# PowerMinder1sch.net
KiCad netlist of a schematic drawn in EAGLE
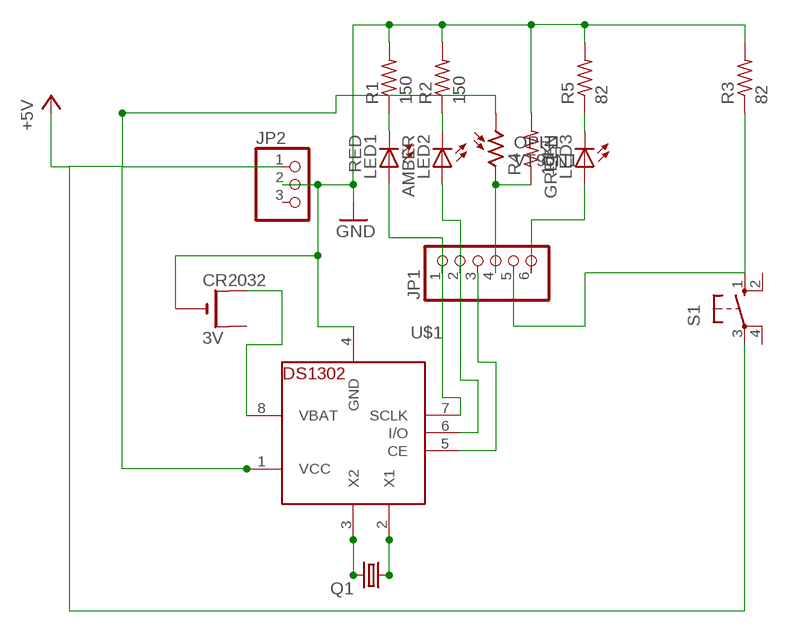
[diagram p0: schematic, sheet 1]

(export (version "E")
  (design (tool "Eeschema 10.0.6"))
  (components
    (comp (ref "CR2032")
      (value "3V")
      (footprint "eagle-import:CR2032-THRU")
      (libsource (lib "eagle-import") (part "CR2032THM"))
    )
    (comp (ref "JP1")
      (value "PINHD-1X6")
      (footprint "eagle-import:1X06")
      (libsource (lib "eagle-import") (part "PINHD-1X6"))
    )
    (comp (ref "JP2")
      (value "PINHD-1X3")
      (footprint "eagle-import:1X03")
      (libsource (lib "eagle-import") (part "PINHD-1X3"))
    )
    (comp (ref "LED1")
      (value "RED")
      (footprint "eagle-import:LED5MM")
      (libsource (lib "eagle-import") (part "LED5MM"))
    )
    (comp (ref "LED2")
      (value "AMBER")
      (footprint "eagle-import:LED5MM")
      (libsource (lib "eagle-import") (part "LED5MM"))
    )
    (comp (ref "LED3")
      (value "GREEN")
      (footprint "eagle-import:LED5MM")
      (libsource (lib "eagle-import") (part "LED5MM"))
    )
    (comp (ref "OPH1")
      (value "VT90N1")
      (footprint "eagle-import:VT900")
      (libsource (lib "eagle-import") (part "VT90N1"))
    )
    (comp (ref "Q1")
      (value "CRYSTALTC26H")
      (footprint "eagle-import:TC26H")
      (libsource (lib "eagle-import") (part "CRYSTALTC26H"))
    )
    (comp (ref "R1")
      (value "150")
      (footprint "eagle-import:0207_12")
      (libsource (lib "eagle-import") (part "R-US_0207/12"))
    )
    (comp (ref "R2")
      (value "150")
      (footprint "eagle-import:0207_12")
      (libsource (lib "eagle-import") (part "R-US_0207/12"))
    )
    (comp (ref "R3")
      (value "82")
      (footprint "eagle-import:0207_12")
      (libsource (lib "eagle-import") (part "R-US_0207/12"))
    )
    (comp (ref "R4")
      (value "10K")
      (footprint "eagle-import:0207_12")
      (libsource (lib "eagle-import") (part "R-US_0207/12"))
    )
    (comp (ref "R5")
      (value "82")
      (footprint "eagle-import:0207_12")
      (libsource (lib "eagle-import") (part "R-US_0207/12"))
    )
    (comp (ref "S1")
      (value "10-XX")
      (footprint "eagle-import:B3F-10XX")
      (fields (field (name "MPN") "B3F-1000"))
      (libsource (lib "eagle-import") (part "10-XX"))
    )
    (comp (ref "U$1")
      (value "DS1302")
      (footprint "eagle-import:DIL08-ROUND")
      (libsource (lib "eagle-import") (part "DS1302"))
    )
  )
  (nets
    (net (code "1") (name "+5V") (class "Default")
      (node (ref "JP2") (pin "1") (pinfunction "1_1") (pintype "passive"))
      (node (ref "OPH1") (pin "1") (pinfunction "1_1") (pintype "passive"))
      (node (ref "S1") (pin "3") (pinfunction "P_3") (pintype "passive"))
      (node (ref "U$1") (pin "1") (pinfunction "VCC_1") (pintype "power_in"))
    )
    (net (code "2") (name "GND") (class "Default")
      (node (ref "CR2032") (pin "-") (pinfunction "-_-") (pintype "passive"))
      (node (ref "JP2") (pin "2") (pinfunction "2_2") (pintype "passive"))
      (node (ref "R1") (pin "2") (pinfunction "2_2") (pintype "passive"))
      (node (ref "R2") (pin "2") (pinfunction "2_2") (pintype "passive"))
      (node (ref "R3") (pin "2") (pinfunction "2_2") (pintype "passive"))
      (node (ref "R4") (pin "2") (pinfunction "2_2") (pintype "passive"))
      (node (ref "R5") (pin "2") (pinfunction "2_2") (pintype "passive"))
      (node (ref "U$1") (pin "4") (pinfunction "GND_4") (pintype "power_in"))
    )
    (net (code "3") (name "Net-(CR2032-+)") (class "Default")
      (node (ref "CR2032") (pin "+1") (pinfunction "+_+1") (pintype "passive"))
      (node (ref "U$1") (pin "8") (pinfunction "VBAT_8") (pintype "power_in"))
    )
    (net (code "4") (name "Net-(JP1-Pad4)") (class "Default")
      (node (ref "JP1") (pin "4") (pinfunction "4_4") (pintype "passive"))
      (node (ref "OPH1") (pin "2") (pinfunction "2_2") (pintype "passive"))
      (node (ref "R4") (pin "1") (pinfunction "1_1") (pintype "passive"))
    )
    (net (code "5") (name "Net-(JP1-Pad6)") (class "Default")
      (node (ref "JP1") (pin "6") (pinfunction "6_6") (pintype "passive"))
      (node (ref "LED3") (pin "A") (pinfunction "A_A") (pintype "passive"))
    )
    (net (code "6") (name "Net-(LED1-C)") (class "Default")
      (node (ref "LED1") (pin "K") (pinfunction "C_K") (pintype "passive"))
      (node (ref "R1") (pin "1") (pinfunction "1_1") (pintype "passive"))
    )
    (net (code "7") (name "Net-(LED2-C)") (class "Default")
      (node (ref "LED2") (pin "K") (pinfunction "C_K") (pintype "passive"))
      (node (ref "R2") (pin "1") (pinfunction "1_1") (pintype "passive"))
    )
    (net (code "8") (name "Net-(LED3-C)") (class "Default")
      (node (ref "LED3") (pin "K") (pinfunction "C_K") (pintype "passive"))
      (node (ref "R5") (pin "1") (pinfunction "1_1") (pintype "passive"))
    )
    (net (code "9") (name "Net-(S1-S)") (class "Default")
      (node (ref "JP1") (pin "5") (pinfunction "5_5") (pintype "passive"))
      (node (ref "R3") (pin "1") (pinfunction "1_1") (pintype "passive"))
      (node (ref "S1") (pin "1") (pinfunction "S_1") (pintype "passive"))
    )
    (net (code "10") (name "Net-(U$1-CE)") (class "Default")
      (node (ref "JP1") (pin "3") (pinfunction "3_3") (pintype "passive"))
      (node (ref "U$1") (pin "5") (pinfunction "CE_5") (pintype "input"))
    )
    (net (code "11") (name "Net-(U$1-I{slash}O)") (class "Default")
      (node (ref "JP1") (pin "2") (pinfunction "2_2") (pintype "passive"))
      (node (ref "LED2") (pin "A") (pinfunction "A_A") (pintype "passive"))
      (node (ref "U$1") (pin "6") (pinfunction "I/O_6") (pintype "bidirectional"))
    )
    (net (code "12") (name "Net-(U$1-SCLK)") (class "Default")
      (node (ref "JP1") (pin "1") (pinfunction "1_1") (pintype "passive"))
      (node (ref "LED1") (pin "A") (pinfunction "A_A") (pintype "passive"))
      (node (ref "U$1") (pin "7") (pinfunction "SCLK_7") (pintype "input"))
    )
    (net (code "13") (name "Net-(U$1-X1)") (class "Default")
      (node (ref "Q1") (pin "1") (pinfunction "1_1") (pintype "passive"))
      (node (ref "U$1") (pin "2") (pinfunction "X1_2") (pintype "passive"))
    )
    (net (code "14") (name "Net-(U$1-X2)") (class "Default")
      (node (ref "Q1") (pin "2") (pinfunction "2_2") (pintype "passive"))
      (node (ref "U$1") (pin "3") (pinfunction "X2_3") (pintype "passive"))
    )
    (net (code "15") (name "unconnected-(CR2032-+1-Pad+2)") (class "Default")
      (node (ref "CR2032") (pin "+2") (pinfunction "+1_+2") (pintype "passive"))
    )
    (net (code "16") (name "unconnected-(JP2-Pad3)") (class "Default")
      (node (ref "JP2") (pin "3") (pinfunction "3_3") (pintype "passive"))
    )
    (net (code "17") (name "unconnected-(S1-P1-Pad4)") (class "Default")
      (node (ref "S1") (pin "4") (pinfunction "P1_4") (pintype "passive"))
    )
    (net (code "18") (name "unconnected-(S1-S1-Pad2)") (class "Default")
      (node (ref "S1") (pin "2") (pinfunction "S1_2") (pintype "passive"))
    )
  )
)
